# LowLevelv2.net
KiCad netlist of a schematic drawn in EAGLE
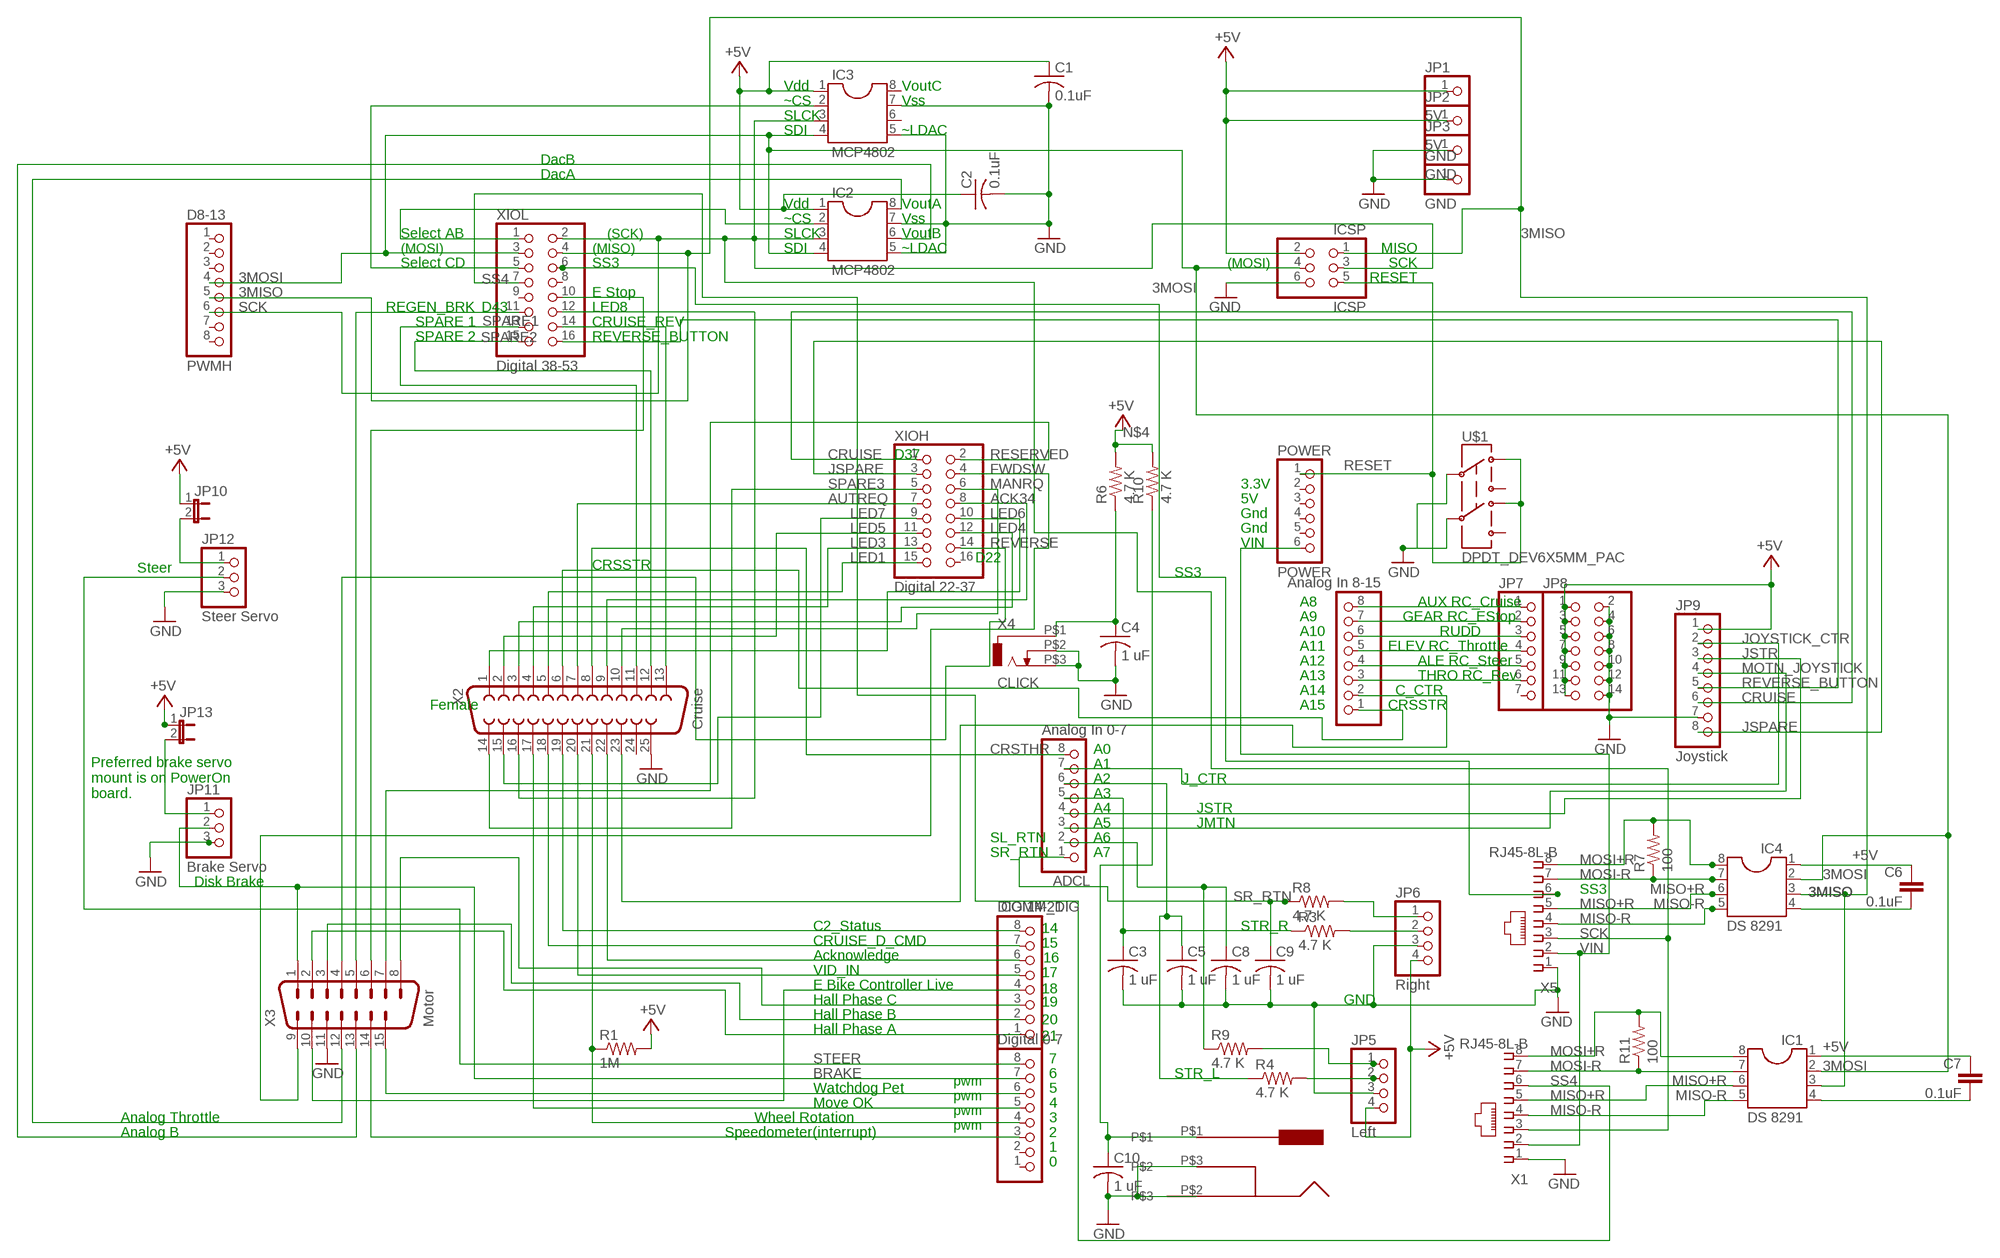
[diagram p0: schematic, sheet 1]

(export (version "E")
  (design (tool "Eeschema 10.0.6"))
  (components
    (comp (ref "ADCH")
      (value "Analog In 8-15")
      (footprint "eagle-import:1X08")
      (libsource (lib "eagle-import") (part "PINHD-1X8"))
    )
    (comp (ref "ADCL")
      (value "Analog In 0-7")
      (footprint "eagle-import:1X08")
      (libsource (lib "eagle-import") (part "PINHD-1X8"))
    )
    (comp (ref "C1")
      (value "0.1uF")
      (footprint "eagle-import:C025-025X050")
      (libsource (lib "eagle-import") (part "C-US025-025X050"))
    )
    (comp (ref "C2")
      (value "0.1uF")
      (footprint "eagle-import:C025-025X050")
      (libsource (lib "eagle-import") (part "C-US025-025X050"))
    )
    (comp (ref "C3")
      (value "1 uF")
      (footprint "eagle-import:C025-030X050")
      (libsource (lib "eagle-import") (part "C-US025-030X050"))
    )
    (comp (ref "C4")
      (value "1 uF")
      (footprint "eagle-import:C025-030X050")
      (libsource (lib "eagle-import") (part "C-US025-030X050"))
    )
    (comp (ref "C5")
      (value "1 uF")
      (footprint "eagle-import:C025-030X050")
      (libsource (lib "eagle-import") (part "C-US025-030X050"))
    )
    (comp (ref "C6")
      (value "0.1uF")
      (footprint "eagle-import:C2.5-2")
      (libsource (lib "eagle-import") (part "C2.5/2"))
    )
    (comp (ref "C7")
      (value "0.1uF")
      (footprint "eagle-import:C2.5-2")
      (libsource (lib "eagle-import") (part "C2.5/2"))
    )
    (comp (ref "C8")
      (value "1 uF")
      (footprint "eagle-import:C025-030X050")
      (libsource (lib "eagle-import") (part "C-US025-030X050"))
    )
    (comp (ref "C9")
      (value "1 uF")
      (footprint "eagle-import:C025-030X050")
      (libsource (lib "eagle-import") (part "C-US025-030X050"))
    )
    (comp (ref "C10")
      (value "1 uF")
      (footprint "eagle-import:C025-030X050")
      (libsource (lib "eagle-import") (part "C-US025-030X050"))
    )
    (comp (ref "COMM_DIG")
      (value "DIG 14-21")
      (footprint "eagle-import:1X08")
      (libsource (lib "eagle-import") (part "PINHD-1X8"))
    )
    (comp (ref "D8-13")
      (value "PWMH")
      (footprint "eagle-import:1X08")
      (libsource (lib "eagle-import") (part "PINHD-1X8"))
    )
    (comp (ref "GND")
      (value "GND")
      (footprint "eagle-import:1X01")
      (libsource (lib "eagle-import") (part "PINHD-1X1"))
    )
    (comp (ref "IC1")
      (value "DS 8291")
      (footprint "eagle-import:DIL08")
      (libsource (lib "eagle-import") (part "DIL8"))
    )
    (comp (ref "IC2")
      (value "MCP4802")
      (footprint "eagle-import:DIL08")
      (libsource (lib "eagle-import") (part "DIL8"))
    )
    (comp (ref "IC3")
      (value "MCP4802")
      (footprint "eagle-import:DIL08")
      (libsource (lib "eagle-import") (part "DIL8"))
    )
    (comp (ref "IC4")
      (value "DS 8291")
      (footprint "eagle-import:DIL08")
      (libsource (lib "eagle-import") (part "DIL8"))
    )
    (comp (ref "ICSP")
      (value "ICSP")
      (footprint "eagle-import:2X03")
      (libsource (lib "eagle-import") (part "PINHD-2X3"))
    )
    (comp (ref "JP1")
      (value "5V")
      (footprint "eagle-import:1X01")
      (libsource (lib "eagle-import") (part "PINHD-1X1"))
    )
    (comp (ref "JP2")
      (value "5V")
      (footprint "eagle-import:1X01")
      (libsource (lib "eagle-import") (part "PINHD-1X1"))
    )
    (comp (ref "JP3")
      (value "GND")
      (footprint "eagle-import:1X01")
      (libsource (lib "eagle-import") (part "PINHD-1X1"))
    )
    (comp (ref "JP5")
      (value "Left")
      (footprint "eagle-import:1X04_90")
      (libsource (lib "eagle-import") (part "PINHD-1X4/90"))
    )
    (comp (ref "JP6")
      (value "Right")
      (footprint "eagle-import:1X04_90")
      (libsource (lib "eagle-import") (part "PINHD-1X4/90"))
    )
    (comp (ref "JP7")
      (value "PINHD-1X7")
      (footprint "eagle-import:1X07")
      (libsource (lib "eagle-import") (part "PINHD-1X7"))
    )
    (comp (ref "JP8")
      (value "PINHD-2X7")
      (footprint "eagle-import:2X07")
      (libsource (lib "eagle-import") (part "PINHD-2X7"))
    )
    (comp (ref "JP9")
      (value "Joystick")
      (footprint "eagle-import:1X08_90")
      (libsource (lib "eagle-import") (part "PINHD-1X8/90"))
    )
    (comp (ref "JP10")
      (value "JP1E")
      (footprint "eagle-import:JP1")
      (libsource (lib "eagle-import") (part "JP1E"))
    )
    (comp (ref "JP11")
      (value "Brake Servo")
      (footprint "eagle-import:1X03_90")
      (libsource (lib "eagle-import") (part "PINHD-1X3/90"))
    )
    (comp (ref "JP12")
      (value "Steer Servo")
      (footprint "eagle-import:1X03_90")
      (libsource (lib "eagle-import") (part "PINHD-1X3/90"))
    )
    (comp (ref "JP13")
      (value "JP1E")
      (footprint "eagle-import:JP1")
      (libsource (lib "eagle-import") (part "JP1E"))
    )
    (comp (ref "POWER")
      (value "POWER")
      (footprint "eagle-import:1X06")
      (libsource (lib "eagle-import") (part "PINHD-1X6"))
    )
    (comp (ref "PWML")
      (value "Digital 0-7")
      (footprint "eagle-import:1X08")
      (libsource (lib "eagle-import") (part "PINHD-1X8"))
    )
    (comp (ref "R1")
      (value "1M")
      (footprint "eagle-import:0207_10")
      (libsource (lib "eagle-import") (part "R-US_0207/10"))
    )
    (comp (ref "R3")
      (value "4.7 K")
      (footprint "eagle-import:0207_10")
      (libsource (lib "eagle-import") (part "R-US_0207/10"))
    )
    (comp (ref "R4")
      (value "4.7 K")
      (footprint "eagle-import:0207_10")
      (libsource (lib "eagle-import") (part "R-US_0207/10"))
    )
    (comp (ref "R6")
      (value "4.7 K")
      (footprint "eagle-import:0207_10")
      (libsource (lib "eagle-import") (part "R-US_0207/10"))
    )
    (comp (ref "R7")
      (value "100")
      (footprint "eagle-import:0207_10")
      (libsource (lib "eagle-import") (part "R-US_0207/10"))
    )
    (comp (ref "R8")
      (value "4.7 K")
      (footprint "eagle-import:0207_10")
      (libsource (lib "eagle-import") (part "R-US_0207/10"))
    )
    (comp (ref "R9")
      (value "4.7 K")
      (footprint "eagle-import:0207_10")
      (libsource (lib "eagle-import") (part "R-US_0207/10"))
    )
    (comp (ref "R10")
      (value "4.7 K")
      (footprint "eagle-import:0207_10")
      (libsource (lib "eagle-import") (part "R-US_0207/10"))
    )
    (comp (ref "R11")
      (value "100")
      (footprint "eagle-import:0207_10")
      (libsource (lib "eagle-import") (part "R-US_0207/10"))
    )
    (comp (ref "U$1")
      (value "DPDT_DEV6X5MM_PAC")
      (footprint "eagle-import:NEWSWITCH2_PAC")
      (libsource (lib "eagle-import") (part "DPDT_DEV6X5MM_PAC"))
    )
    (comp (ref "U$2")
      (value "CUI_JACKTHROUGH_HOLE")
      (footprint "eagle-import:CUIJACK")
      (libsource (lib "eagle-import") (part "CUI_JACKTHROUGH_HOLE"))
    )
    (comp (ref "X1")
      (value "RJ45-8L-B")
      (footprint "eagle-import:RJ45-NO-SHIELD")
      (fields (field (name "MF") "TYCO ELECTRONICS"))
      (libsource (lib "eagle-import") (part "RJ45-8L-B"))
    )
    (comp (ref "X2")
      (value "Cruise")
      (footprint "eagle-import:F25H")
      (libsource (lib "eagle-import") (part "F25H"))
    )
    (comp (ref "X3")
      (value "Motor")
      (footprint "eagle-import:182-015-MALE")
      (libsource (lib "eagle-import") (part "M15-182"))
    )
    (comp (ref "X4")
      (value "CLICK")
      (footprint "eagle-import:ODO_JACK")
      (libsource (lib "eagle-import") (part "ODO_JACK"))
    )
    (comp (ref "X5")
      (value "RJ45-8L-B")
      (footprint "eagle-import:RJ45-NO-SHIELD")
      (fields (field (name "MF") "TYCO ELECTRONICS"))
      (libsource (lib "eagle-import") (part "RJ45-8L-B"))
    )
    (comp (ref "XIOH")
      (value "Digital 22-37")
      (footprint "eagle-import:2X08")
      (libsource (lib "eagle-import") (part "PINHD-2X8"))
    )
    (comp (ref "XIOL")
      (value "Digital 38-53")
      (footprint "eagle-import:2X08")
      (libsource (lib "eagle-import") (part "PINHD-2X8"))
    )
  )
  (nets
    (net (code "1") (name "+5V") (class "Default")
      (node (ref "C1") (pin "1") (pinfunction "1_1") (pintype "passive"))
      (node (ref "C2") (pin "1") (pinfunction "1_1") (pintype "passive"))
      (node (ref "C6") (pin "1") (pinfunction "1_1") (pintype "passive"))
      (node (ref "IC2") (pin "1") (pinfunction "1_1") (pintype "passive"))
      (node (ref "IC3") (pin "1") (pinfunction "1_1") (pintype "passive"))
      (node (ref "IC4") (pin "1") (pinfunction "1_1") (pintype "passive"))
      (node (ref "ICSP") (pin "2") (pinfunction "2_2") (pintype "passive"))
      (node (ref "JP1") (pin "1") (pinfunction "1_1") (pintype "passive"))
      (node (ref "JP10") (pin "1") (pinfunction "1_1") (pintype "passive"))
      (node (ref "JP13") (pin "1") (pinfunction "1_1") (pintype "passive"))
      (node (ref "JP2") (pin "1") (pinfunction "1_1") (pintype "passive"))
      (node (ref "JP5") (pin "4") (pinfunction "4_4") (pintype "passive"))
      (node (ref "JP6") (pin "4") (pinfunction "4_4") (pintype "passive"))
      (node (ref "JP8") (pin "1") (pinfunction "1_1") (pintype "passive"))
      (node (ref "JP8") (pin "11") (pinfunction "11_11") (pintype "passive"))
      (node (ref "JP8") (pin "13") (pinfunction "13_13") (pintype "passive"))
      (node (ref "JP8") (pin "3") (pinfunction "3_3") (pintype "passive"))
      (node (ref "JP8") (pin "5") (pinfunction "5_5") (pintype "passive"))
      (node (ref "JP8") (pin "7") (pinfunction "7_7") (pintype "passive"))
      (node (ref "JP8") (pin "9") (pinfunction "9_9") (pintype "passive"))
      (node (ref "JP9") (pin "1") (pinfunction "1_1") (pintype "passive"))
      (node (ref "R1") (pin "2") (pinfunction "2_2") (pintype "passive"))
      (node (ref "R10") (pin "2") (pinfunction "2_2") (pintype "passive"))
      (node (ref "R6") (pin "2") (pinfunction "2_2") (pintype "passive"))
    )
    (net (code "2") (name "3MISO") (class "Default")
      (node (ref "D8-13") (pin "5") (pinfunction "5_5") (pintype "passive"))
      (node (ref "IC1") (pin "3") (pinfunction "3_3") (pintype "passive"))
      (node (ref "IC4") (pin "3") (pinfunction "3_3") (pintype "passive"))
      (node (ref "ICSP") (pin "1") (pinfunction "1_1") (pintype "passive"))
      (node (ref "XIOL") (pin "4") (pinfunction "4_4") (pintype "passive"))
    )
    (net (code "3") (name "3MOSI") (class "Default")
      (node (ref "D8-13") (pin "4") (pinfunction "4_4") (pintype "passive"))
      (node (ref "IC1") (pin "2") (pinfunction "2_2") (pintype "passive"))
      (node (ref "IC2") (pin "4") (pinfunction "4_4") (pintype "passive"))
      (node (ref "IC3") (pin "4") (pinfunction "4_4") (pintype "passive"))
      (node (ref "IC4") (pin "2") (pinfunction "2_2") (pintype "passive"))
      (node (ref "ICSP") (pin "4") (pinfunction "4_4") (pintype "passive"))
      (node (ref "XIOL") (pin "3") (pinfunction "3_3") (pintype "passive"))
    )
    (net (code "4") (name "ACK34") (class "Default")
      (node (ref "X2") (pin "9") (pinfunction "9_9") (pintype "passive"))
      (node (ref "XIOH") (pin "8") (pinfunction "8_8") (pintype "passive"))
    )
    (net (code "5") (name "AUTREQ") (class "Default")
      (node (ref "X2") (pin "7") (pinfunction "7_7") (pintype "passive"))
      (node (ref "XIOH") (pin "7") (pinfunction "7_7") (pintype "passive"))
    )
    (net (code "6") (name "BRAKE") (class "Default")
      (node (ref "JP11") (pin "2") (pinfunction "2_2") (pintype "passive"))
      (node (ref "PWML") (pin "7") (pinfunction "7_7") (pintype "passive"))
      (node (ref "X3") (pin "1") (pinfunction "1_1") (pintype "passive"))
    )
    (net (code "7") (name "CRSTHR") (class "Default")
      (node (ref "ADCL") (pin "8") (pinfunction "8_8") (pintype "passive"))
      (node (ref "X2") (pin "8") (pinfunction "8_8") (pintype "passive"))
    )
    (net (code "8") (name "CRUISE") (class "Default")
      (node (ref "JP9") (pin "6") (pinfunction "6_6") (pintype "passive"))
      (node (ref "XIOH") (pin "1") (pinfunction "1_1") (pintype "passive"))
    )
    (net (code "9") (name "CRUISE_D_CMD") (class "Default")
      (node (ref "COMM_DIG") (pin "7") (pinfunction "7_7") (pintype "passive"))
      (node (ref "X2") (pin "18") (pinfunction "18_18") (pintype "passive"))
    )
    (net (code "10") (name "CRUISE_REV") (class "Default")
      (node (ref "X2") (pin "13") (pinfunction "13_13") (pintype "passive"))
      (node (ref "XIOL") (pin "14") (pinfunction "14_14") (pintype "passive"))
    )
    (net (code "11") (name "FWDSW") (class "Default")
      (node (ref "X3") (pin "9") (pinfunction "9_9") (pintype "passive"))
      (node (ref "XIOH") (pin "4") (pinfunction "4_4") (pintype "passive"))
    )
    (net (code "12") (name "GND") (class "Default")
      (node (ref "C1") (pin "2") (pinfunction "2_2") (pintype "passive"))
      (node (ref "C10") (pin "2") (pinfunction "2_2") (pintype "passive"))
      (node (ref "C2") (pin "2") (pinfunction "2_2") (pintype "passive"))
      (node (ref "C3") (pin "2") (pinfunction "2_2") (pintype "passive"))
      (node (ref "C4") (pin "2") (pinfunction "2_2") (pintype "passive"))
      (node (ref "C5") (pin "2") (pinfunction "2_2") (pintype "passive"))
      (node (ref "C8") (pin "2") (pinfunction "2_2") (pintype "passive"))
      (node (ref "C9") (pin "2") (pinfunction "2_2") (pintype "passive"))
      (node (ref "GND") (pin "1") (pinfunction "1_1") (pintype "passive"))
      (node (ref "IC2") (pin "5") (pinfunction "5_5") (pintype "passive"))
      (node (ref "IC2") (pin "7") (pinfunction "7_7") (pintype "passive"))
      (node (ref "IC3") (pin "5") (pinfunction "5_5") (pintype "passive"))
      (node (ref "IC3") (pin "7") (pinfunction "7_7") (pintype "passive"))
      (node (ref "ICSP") (pin "6") (pinfunction "6_6") (pintype "passive"))
      (node (ref "JP11") (pin "3") (pinfunction "3_3") (pintype "passive"))
      (node (ref "JP12") (pin "3") (pinfunction "3_3") (pintype "passive"))
      (node (ref "JP3") (pin "1") (pinfunction "1_1") (pintype "passive"))
      (node (ref "JP5") (pin "3") (pinfunction "3_3") (pintype "passive"))
      (node (ref "JP6") (pin "3") (pinfunction "3_3") (pintype "passive"))
      (node (ref "JP8") (pin "10") (pinfunction "10_10") (pintype "passive"))
      (node (ref "JP8") (pin "12") (pinfunction "12_12") (pintype "passive"))
      (node (ref "JP8") (pin "14") (pinfunction "14_14") (pintype "passive"))
      (node (ref "JP8") (pin "2") (pinfunction "2_2") (pintype "passive"))
      (node (ref "JP8") (pin "4") (pinfunction "4_4") (pintype "passive"))
      (node (ref "JP8") (pin "6") (pinfunction "6_6") (pintype "passive"))
      (node (ref "JP8") (pin "8") (pinfunction "8_8") (pintype "passive"))
      (node (ref "JP9") (pin "7") (pinfunction "7_7") (pintype "passive"))
      (node (ref "U$1") (pin "PIN2") (pinfunction "2_PIN2") (pintype "bidirectional"))
      (node (ref "U$1") (pin "PIN5") (pinfunction "5_PIN5") (pintype "bidirectional"))
      (node (ref "U$2") (pin "P$2") (pinfunction "P$3_P$2") (pintype "bidirectional"))
      (node (ref "U$2") (pin "P$3") (pinfunction "P$2_P$3") (pintype "bidirectional"))
      (node (ref "X1") (pin "1") (pinfunction "1_1") (pintype "passive"))
      (node (ref "X2") (pin "25") (pinfunction "25_25") (pintype "passive"))
      (node (ref "X3") (pin "11") (pinfunction "11_11") (pintype "passive"))
      (node (ref "X4") (pin "P$2") (pinfunction "2_P$2") (pintype "passive"))
      (node (ref "X4") (pin "P$3") (pinfunction "3_P$3") (pintype "passive"))
      (node (ref "X5") (pin "1") (pinfunction "1_1") (pintype "passive"))
    )
    (net (code "13") (name "JOYSTICK_CTR") (class "Default")
      (node (ref "ADCL") (pin "7") (pinfunction "7_7") (pintype "passive"))
      (node (ref "JP9") (pin "2") (pinfunction "2_2") (pintype "passive"))
    )
    (net (code "14") (name "JSPARE") (class "Default")
      (node (ref "JP9") (pin "8") (pinfunction "8_8") (pintype "passive"))
      (node (ref "XIOH") (pin "3") (pinfunction "3_3") (pintype "passive"))
    )
    (net (code "15") (name "JSTR") (class "Default")
      (node (ref "ADCL") (pin "4") (pinfunction "4_4") (pintype "passive"))
      (node (ref "JP9") (pin "3") (pinfunction "3_3") (pintype "passive"))
    )
    (net (code "16") (name "LED1") (class "Default")
      (node (ref "X2") (pin "5") (pinfunction "5_5") (pintype "passive"))
      (node (ref "XIOH") (pin "15") (pinfunction "15_15") (pintype "passive"))
    )
    (net (code "17") (name "LED3") (class "Default")
      (node (ref "X2") (pin "4") (pinfunction "4_4") (pintype "passive"))
      (node (ref "XIOH") (pin "13") (pinfunction "13_13") (pintype "passive"))
    )
    (net (code "18") (name "LED4") (class "Default")
      (node (ref "X2") (pin "3") (pinfunction "3_3") (pintype "passive"))
      (node (ref "XIOH") (pin "12") (pinfunction "12_12") (pintype "passive"))
    )
    (net (code "19") (name "LED5") (class "Default")
      (node (ref "X2") (pin "2") (pinfunction "2_2") (pintype "passive"))
      (node (ref "XIOH") (pin "11") (pinfunction "11_11") (pintype "passive"))
    )
    (net (code "20") (name "LED6") (class "Default")
      (node (ref "X2") (pin "1") (pinfunction "1_1") (pintype "passive"))
      (node (ref "XIOH") (pin "10") (pinfunction "10_10") (pintype "passive"))
    )
    (net (code "21") (name "LED7") (class "Default")
      (node (ref "X2") (pin "15") (pinfunction "15_15") (pintype "passive"))
      (node (ref "XIOH") (pin "9") (pinfunction "9_9") (pintype "passive"))
    )
    (net (code "22") (name "LED8") (class "Default")
      (node (ref "X2") (pin "16") (pinfunction "16_16") (pintype "passive"))
      (node (ref "XIOL") (pin "12") (pinfunction "12_12") (pintype "passive"))
    )
    (net (code "23") (name "MANRQ") (class "Default")
      (node (ref "X2") (pin "10") (pinfunction "10_10") (pintype "passive"))
      (node (ref "XIOH") (pin "6") (pinfunction "6_6") (pintype "passive"))
    )
    (net (code "24") (name "MISO+R") (class "Default")
      (node (ref "IC1") (pin "6") (pinfunction "6_6") (pintype "passive"))
      (node (ref "IC4") (pin "6") (pinfunction "6_6") (pintype "passive"))
      (node (ref "X1") (pin "5") (pinfunction "5_5") (pintype "passive"))
      (node (ref "X5") (pin "5") (pinfunction "5_5") (pintype "passive"))
    )
    (net (code "25") (name "MISO-R") (class "Default")
      (node (ref "IC1") (pin "5") (pinfunction "5_5") (pintype "passive"))
      (node (ref "IC4") (pin "5") (pinfunction "5_5") (pintype "passive"))
      (node (ref "X1") (pin "4") (pinfunction "4_4") (pintype "passive"))
      (node (ref "X5") (pin "4") (pinfunction "4_4") (pintype "passive"))
    )
    (net (code "26") (name "MOSI+R") (class "Default")
      (node (ref "IC1") (pin "8") (pinfunction "8_8") (pintype "passive"))
      (node (ref "IC4") (pin "8") (pinfunction "8_8") (pintype "passive"))
      (node (ref "R11") (pin "2") (pinfunction "2_2") (pintype "passive"))
      (node (ref "R7") (pin "2") (pinfunction "2_2") (pintype "passive"))
      (node (ref "X1") (pin "8") (pinfunction "8_8") (pintype "passive"))
      (node (ref "X5") (pin "8") (pinfunction "8_8") (pintype "passive"))
    )
    (net (code "27") (name "MOSI-R") (class "Default")
      (node (ref "IC1") (pin "7") (pinfunction "7_7") (pintype "passive"))
      (node (ref "IC4") (pin "7") (pinfunction "7_7") (pintype "passive"))
      (node (ref "R11") (pin "1") (pinfunction "1_1") (pintype "passive"))
      (node (ref "R7") (pin "1") (pinfunction "1_1") (pintype "passive"))
      (node (ref "X1") (pin "7") (pinfunction "7_7") (pintype "passive"))
      (node (ref "X5") (pin "7") (pinfunction "7_7") (pintype "passive"))
    )
    (net (code "28") (name "MOTN_JOYSTICK") (class "Default")
      (node (ref "ADCL") (pin "3") (pinfunction "3_3") (pintype "passive"))
      (node (ref "JP9") (pin "4") (pinfunction "4_4") (pintype "passive"))
    )
    (net (code "29") (name "N$4") (class "Default")
      (node (ref "C4") (pin "1") (pinfunction "1_1") (pintype "passive"))
      (node (ref "R6") (pin "1") (pinfunction "1_1") (pintype "passive"))
      (node (ref "X4") (pin "P$1") (pinfunction "1_P$1") (pintype "passive"))
    )
    (net (code "30") (name "Net-(ADCH-Pad1)") (class "Default")
      (node (ref "ADCH") (pin "1") (pinfunction "1_1") (pintype "passive"))
      (node (ref "X2") (pin "6") (pinfunction "6_6") (pintype "passive"))
    )
    (net (code "31") (name "Net-(ADCH-Pad2)") (class "Default")
      (node (ref "ADCH") (pin "2") (pinfunction "2_2") (pintype "passive"))
      (node (ref "X2") (pin "23") (pinfunction "23_23") (pintype "passive"))
    )
    (net (code "32") (name "Net-(ADCH-Pad3)") (class "Default")
      (node (ref "ADCH") (pin "3") (pinfunction "3_3") (pintype "passive"))
      (node (ref "JP7") (pin "6") (pinfunction "6_6") (pintype "passive"))
    )
    (net (code "33") (name "Net-(ADCH-Pad4)") (class "Default")
      (node (ref "ADCH") (pin "4") (pinfunction "4_4") (pintype "passive"))
      (node (ref "JP7") (pin "5") (pinfunction "5_5") (pintype "passive"))
    )
    (net (code "34") (name "Net-(ADCH-Pad5)") (class "Default")
      (node (ref "ADCH") (pin "5") (pinfunction "5_5") (pintype "passive"))
      (node (ref "JP7") (pin "4") (pinfunction "4_4") (pintype "passive"))
    )
    (net (code "35") (name "Net-(ADCH-Pad6)") (class "Default")
      (node (ref "ADCH") (pin "6") (pinfunction "6_6") (pintype "passive"))
      (node (ref "JP7") (pin "3") (pinfunction "3_3") (pintype "passive"))
    )
    (net (code "36") (name "Net-(ADCH-Pad7)") (class "Default")
      (node (ref "ADCH") (pin "7") (pinfunction "7_7") (pintype "passive"))
      (node (ref "JP7") (pin "2") (pinfunction "2_2") (pintype "passive"))
    )
    (net (code "37") (name "Net-(ADCH-Pad8)") (class "Default")
      (node (ref "ADCH") (pin "8") (pinfunction "8_8") (pintype "passive"))
      (node (ref "JP7") (pin "1") (pinfunction "1_1") (pintype "passive"))
    )
    (net (code "38") (name "Net-(ADCL-Pad2)") (class "Default")
      (node (ref "ADCL") (pin "2") (pinfunction "2_2") (pintype "passive"))
      (node (ref "C8") (pin "1") (pinfunction "1_1") (pintype "passive"))
      (node (ref "R9") (pin "1") (pinfunction "1_1") (pintype "passive"))
    )
    (net (code "39") (name "Net-(ADCL-Pad5)") (class "Default")
      (node (ref "ADCL") (pin "5") (pinfunction "5_5") (pintype "passive"))
      (node (ref "C3") (pin "1") (pinfunction "1_1") (pintype "passive"))
      (node (ref "R3") (pin "1") (pinfunction "1_1") (pintype "passive"))
    )
    (net (code "40") (name "Net-(ADCL-Pad6)") (class "Default")
      (node (ref "ADCL") (pin "6") (pinfunction "6_6") (pintype "passive"))
      (node (ref "C5") (pin "1") (pinfunction "1_1") (pintype "passive"))
      (node (ref "R4") (pin "1") (pinfunction "1_1") (pintype "passive"))
    )
    (net (code "41") (name "Net-(C6-Pad2)") (class "Default")
      (node (ref "C6") (pin "2") (pinfunction "2_2") (pintype "passive"))
      (node (ref "IC4") (pin "4") (pinfunction "4_4") (pintype "passive"))
    )
    (net (code "42") (name "Net-(C7-Pad1)") (class "Default")
      (node (ref "C7") (pin "1") (pinfunction "1_1") (pintype "passive"))
      (node (ref "IC1") (pin "1") (pinfunction "1_1") (pintype "passive"))
    )
    (net (code "43") (name "Net-(C7-Pad2)") (class "Default")
      (node (ref "C7") (pin "2") (pinfunction "2_2") (pintype "passive"))
      (node (ref "IC1") (pin "4") (pinfunction "4_4") (pintype "passive"))
    )
    (net (code "44") (name "Net-(C10-Pad1)") (class "Default")
      (node (ref "C10") (pin "1") (pinfunction "1_1") (pintype "passive"))
      (node (ref "R10") (pin "1") (pinfunction "1_1") (pintype "passive"))
      (node (ref "U$2") (pin "P$1") (pinfunction "P$1_P$1") (pintype "bidirectional"))
    )
    (net (code "45") (name "Net-(COMM_DIG-Pad1)") (class "Default")
      (node (ref "COMM_DIG") (pin "1") (pinfunction "1_1") (pintype "passive"))
      (node (ref "X3") (pin "2") (pinfunction "2_2") (pintype "passive"))
    )
    (net (code "46") (name "Net-(COMM_DIG-Pad2)") (class "Default")
      (node (ref "COMM_DIG") (pin "2") (pinfunction "2_2") (pintype "passive"))
      (node (ref "X3") (pin "3") (pinfunction "3_3") (pintype "passive"))
    )
    (net (code "47") (name "Net-(COMM_DIG-Pad3)") (class "Default")
      (node (ref "COMM_DIG") (pin "3") (pinfunction "3_3") (pintype "passive"))
      (node (ref "X3") (pin "8") (pinfunction "8_8") (pintype "passive"))
    )
    (net (code "48") (name "Net-(COMM_DIG-Pad4)") (class "Default")
      (node (ref "COMM_DIG") (pin "4") (pinfunction "4_4") (pintype "passive"))
      (node (ref "X3") (pin "10") (pinfunction "10_10") (pintype "passive"))
    )
    (net (code "49") (name "Net-(COMM_DIG-Pad5)") (class "Default")
      (node (ref "COMM_DIG") (pin "5") (pinfunction "5_5") (pintype "passive"))
      (node (ref "X2") (pin "20") (pinfunction "20_20") (pintype "passive"))
    )
    (net (code "50") (name "Net-(COMM_DIG-Pad6)") (class "Default")
      (node (ref "COMM_DIG") (pin "6") (pinfunction "6_6") (pintype "passive"))
      (node (ref "X2") (pin "22") (pinfunction "22_22") (pintype "passive"))
    )
    (net (code "51") (name "Net-(COMM_DIG-Pad8)") (class "Default")
      (node (ref "COMM_DIG") (pin "8") (pinfunction "8_8") (pintype "passive"))
      (node (ref "X2") (pin "19") (pinfunction "19_19") (pintype "passive"))
    )
    (net (code "52") (name "Net-(IC2-Pad2)") (class "Default")
      (node (ref "IC2") (pin "2") (pinfunction "2_2") (pintype "passive"))
      (node (ref "XIOL") (pin "1") (pinfunction "1_1") (pintype "passive"))
    )
    (net (code "53") (name "Net-(IC2-Pad6)") (class "Default")
      (node (ref "IC2") (pin "6") (pinfunction "6_6") (pintype "passive"))
      (node (ref "X3") (pin "13") (pinfunction "13_13") (pintype "passive"))
    )
    (net (code "54") (name "Net-(IC2-Pad8)") (class "Default")
      (node (ref "IC2") (pin "8") (pinfunction "8_8") (pintype "passive"))
      (node (ref "X3") (pin "12") (pinfunction "12_12") (pintype "passive"))
    )
    (net (code "55") (name "Net-(IC3-Pad2)") (class "Default")
      (node (ref "IC3") (pin "2") (pinfunction "2_2") (pintype "passive"))
      (node (ref "XIOL") (pin "5") (pinfunction "5_5") (pintype "passive"))
    )
    (net (code "56") (name "Net-(JP5-Pad1)") (class "Default")
      (node (ref "JP5") (pin "1") (pinfunction "1_1") (pintype "passive"))
      (node (ref "R9") (pin "2") (pinfunction "2_2") (pintype "passive"))
    )
    (net (code "57") (name "Net-(JP5-Pad2)") (class "Default")
      (node (ref "JP5") (pin "2") (pinfunction "2_2") (pintype "passive"))
      (node (ref "R4") (pin "2") (pinfunction "2_2") (pintype "passive"))
    )
    (net (code "58") (name "Net-(JP6-Pad1)") (class "Default")
      (node (ref "JP6") (pin "1") (pinfunction "1_1") (pintype "passive"))
      (node (ref "R8") (pin "2") (pinfunction "2_2") (pintype "passive"))
    )
    (net (code "59") (name "Net-(JP6-Pad2)") (class "Default")
      (node (ref "JP6") (pin "2") (pinfunction "2_2") (pintype "passive"))
      (node (ref "R3") (pin "2") (pinfunction "2_2") (pintype "passive"))
    )
    (net (code "60") (name "Net-(JP10-Pad2)") (class "Default")
      (node (ref "JP10") (pin "2") (pinfunction "2_2") (pintype "passive"))
      (node (ref "JP12") (pin "1") (pinfunction "1_1") (pintype "passive"))
    )
    (net (code "61") (name "Net-(JP11-Pad1)") (class "Default")
      (node (ref "JP11") (pin "1") (pinfunction "1_1") (pintype "passive"))
      (node (ref "JP13") (pin "2") (pinfunction "2_2") (pintype "passive"))
    )
    (net (code "62") (name "Net-(PWML-Pad3)") (class "Default")
      (node (ref "PWML") (pin "3") (pinfunction "3_3") (pintype "passive"))
      (node (ref "X3") (pin "14") (pinfunction "14_14") (pintype "passive"))
    )
    (net (code "63") (name "Net-(PWML-Pad4)") (class "Default")
      (node (ref "PWML") (pin "4") (pinfunction "4_4") (pintype "passive"))
      (node (ref "R1") (pin "1") (pinfunction "1_1") (pintype "passive"))
      (node (ref "X2") (pin "21") (pinfunction "21_21") (pintype "passive"))
    )
    (net (code "64") (name "Net-(PWML-Pad5)") (class "Default")
      (node (ref "PWML") (pin "5") (pinfunction "5_5") (pintype "passive"))
      (node (ref "X2") (pin "17") (pinfunction "17_17") (pintype "passive"))
    )
    (net (code "65") (name "Net-(PWML-Pad6)") (class "Default")
      (node (ref "PWML") (pin "6") (pinfunction "6_6") (pintype "passive"))
      (node (ref "X3") (pin "15") (pinfunction "15_15") (pintype "passive"))
    )
    (net (code "66") (name "Net-(X3-Pad5)") (class "Default")
      (node (ref "X3") (pin "5") (pinfunction "5_5") (pintype "passive"))
      (node (ref "XIOL") (pin "11") (pinfunction "11_11") (pintype "passive"))
    )
    (net (code "67") (name "Net-(X3-Pad6)") (class "Default")
      (node (ref "X3") (pin "6") (pinfunction "6_6") (pintype "passive"))
      (node (ref "XIOL") (pin "10") (pinfunction "10_10") (pintype "passive"))
    )
    (net (code "68") (name "Net-(X5-Pad6)") (class "Default")
      (node (ref "X5") (pin "6") (pinfunction "6_6") (pintype "passive"))
      (node (ref "XIOL") (pin "6") (pinfunction "6_6") (pintype "passive"))
    )
    (net (code "69") (name "RESERVED") (class "Default")
      (node (ref "X3") (pin "7") (pinfunction "7_7") (pintype "passive"))
      (node (ref "XIOH") (pin "2") (pinfunction "2_2") (pintype "passive"))
    )
    (net (code "70") (name "RESET") (class "Default")
      (node (ref "ICSP") (pin "5") (pinfunction "5_5") (pintype "passive"))
      (node (ref "POWER") (pin "1") (pinfunction "1_1") (pintype "passive"))
      (node (ref "U$1") (pin "PIN1") (pinfunction "1_PIN1") (pintype "bidirectional"))
      (node (ref "U$1") (pin "PIN4") (pinfunction "4_PIN4") (pintype "bidirectional"))
    )
    (net (code "71") (name "REVERSE") (class "Default")
      (node (ref "X3") (pin "4") (pinfunction "4_4") (pintype "passive"))
      (node (ref "XIOH") (pin "14") (pinfunction "14_14") (pintype "passive"))
    )
    (net (code "72") (name "REVERSE_BUTTON") (class "Default")
      (node (ref "JP9") (pin "5") (pinfunction "5_5") (pintype "passive"))
      (node (ref "XIOL") (pin "16") (pinfunction "16_16") (pintype "passive"))
    )
    (net (code "73") (name "SCK") (class "Default")
      (node (ref "D8-13") (pin "6") (pinfunction "6_6") (pintype "passive"))
      (node (ref "IC2") (pin "3") (pinfunction "3_3") (pintype "passive"))
      (node (ref "IC3") (pin "3") (pinfunction "3_3") (pintype "passive"))
      (node (ref "ICSP") (pin "3") (pinfunction "3_3") (pintype "passive"))
      (node (ref "X1") (pin "3") (pinfunction "3_3") (pintype "passive"))
      (node (ref "X5") (pin "3") (pinfunction "3_3") (pintype "passive"))
      (node (ref "XIOL") (pin "2") (pinfunction "2_2") (pintype "passive"))
    )
    (net (code "74") (name "SPARE1") (class "Default")
      (node (ref "X2") (pin "11") (pinfunction "11_11") (pintype "passive"))
      (node (ref "XIOL") (pin "13") (pinfunction "13_13") (pintype "passive"))
    )
    (net (code "75") (name "SPARE2") (class "Default")
      (node (ref "X2") (pin "12") (pinfunction "12_12") (pintype "passive"))
      (node (ref "XIOL") (pin "15") (pinfunction "15_15") (pintype "passive"))
    )
    (net (code "76") (name "SPARE3") (class "Default")
      (node (ref "X2") (pin "14") (pinfunction "14_14") (pintype "passive"))
      (node (ref "XIOH") (pin "5") (pinfunction "5_5") (pintype "passive"))
    )
    (net (code "77") (name "SR_RTN") (class "Default")
      (node (ref "ADCL") (pin "1") (pinfunction "1_1") (pintype "passive"))
      (node (ref "C9") (pin "1") (pinfunction "1_1") (pintype "passive"))
      (node (ref "R8") (pin "1") (pinfunction "1_1") (pintype "passive"))
    )
    (net (code "78") (name "SS4") (class "Default")
      (node (ref "X1") (pin "6") (pinfunction "6_6") (pintype "passive"))
      (node (ref "XIOL") (pin "7") (pinfunction "7_7") (pintype "passive"))
    )
    (net (code "79") (name "STEER") (class "Default")
      (node (ref "JP12") (pin "2") (pinfunction "2_2") (pintype "passive"))
      (node (ref "PWML") (pin "8") (pinfunction "8_8") (pintype "passive"))
    )
    (net (code "80") (name "VIN") (class "Default")
      (node (ref "POWER") (pin "6") (pinfunction "6_6") (pintype "passive"))
      (node (ref "X1") (pin "2") (pinfunction "2_2") (pintype "passive"))
      (node (ref "X5") (pin "2") (pinfunction "2_2") (pintype "passive"))
    )
    (net (code "81") (name "unconnected-(D8-13-Pad1)") (class "Default")
      (node (ref "D8-13") (pin "1") (pinfunction "1_1") (pintype "passive"))
    )
    (net (code "82") (name "unconnected-(D8-13-Pad2)") (class "Default")
      (node (ref "D8-13") (pin "2") (pinfunction "2_2") (pintype "passive"))
    )
    (net (code "83") (name "unconnected-(D8-13-Pad3)") (class "Default")
      (node (ref "D8-13") (pin "3") (pinfunction "3_3") (pintype "passive"))
    )
    (net (code "84") (name "unconnected-(D8-13-Pad7)") (class "Default")
      (node (ref "D8-13") (pin "7") (pinfunction "7_7") (pintype "passive"))
    )
    (net (code "85") (name "unconnected-(D8-13-Pad8)") (class "Default")
      (node (ref "D8-13") (pin "8") (pinfunction "8_8") (pintype "passive"))
    )
    (net (code "86") (name "unconnected-(IC3-Pad6)") (class "Default")
      (node (ref "IC3") (pin "6") (pinfunction "6_6") (pintype "passive"))
    )
    (net (code "87") (name "unconnected-(IC3-Pad8)") (class "Default")
      (node (ref "IC3") (pin "8") (pinfunction "8_8") (pintype "passive"))
    )
    (net (code "88") (name "unconnected-(JP7-Pad7)") (class "Default")
      (node (ref "JP7") (pin "7") (pinfunction "7_7") (pintype "passive"))
    )
    (net (code "89") (name "unconnected-(POWER-Pad2)") (class "Default")
      (node (ref "POWER") (pin "2") (pinfunction "2_2") (pintype "passive"))
    )
    (net (code "90") (name "unconnected-(POWER-Pad3)") (class "Default")
      (node (ref "POWER") (pin "3") (pinfunction "3_3") (pintype "passive"))
    )
    (net (code "91") (name "unconnected-(POWER-Pad4)") (class "Default")
      (node (ref "POWER") (pin "4") (pinfunction "4_4") (pintype "passive"))
    )
    (net (code "92") (name "unconnected-(POWER-Pad5)") (class "Default")
      (node (ref "POWER") (pin "5") (pinfunction "5_5") (pintype "passive"))
    )
    (net (code "93") (name "unconnected-(PWML-Pad1)") (class "Default")
      (node (ref "PWML") (pin "1") (pinfunction "1_1") (pintype "passive"))
    )
    (net (code "94") (name "unconnected-(PWML-Pad2)") (class "Default")
      (node (ref "PWML") (pin "2") (pinfunction "2_2") (pintype "passive"))
    )
    (net (code "95") (name "unconnected-(U$1-3-PadPIN3)") (class "Default")
      (node (ref "U$1") (pin "PIN3") (pinfunction "3_PIN3") (pintype "bidirectional"))
    )
    (net (code "96") (name "unconnected-(U$1-6-PadPIN6)") (class "Default")
      (node (ref "U$1") (pin "PIN6") (pinfunction "6_PIN6") (pintype "bidirectional"))
    )
    (net (code "97") (name "unconnected-(X2-Pad24)") (class "Default")
      (node (ref "X2") (pin "24") (pinfunction "24_24") (pintype "passive"))
    )
    (net (code "98") (name "unconnected-(XIOH-Pad16)") (class "Default")
      (node (ref "XIOH") (pin "16") (pinfunction "16_16") (pintype "passive"))
    )
    (net (code "99") (name "unconnected-(XIOL-Pad8)") (class "Default")
      (node (ref "XIOL") (pin "8") (pinfunction "8_8") (pintype "passive"))
    )
    (net (code "100") (name "unconnected-(XIOL-Pad9)") (class "Default")
      (node (ref "XIOL") (pin "9") (pinfunction "9_9") (pintype "passive"))
    )
  )
)
